# 5_-Keyboard.net
KiCad netlist of a schematic drawn in Altium Designer
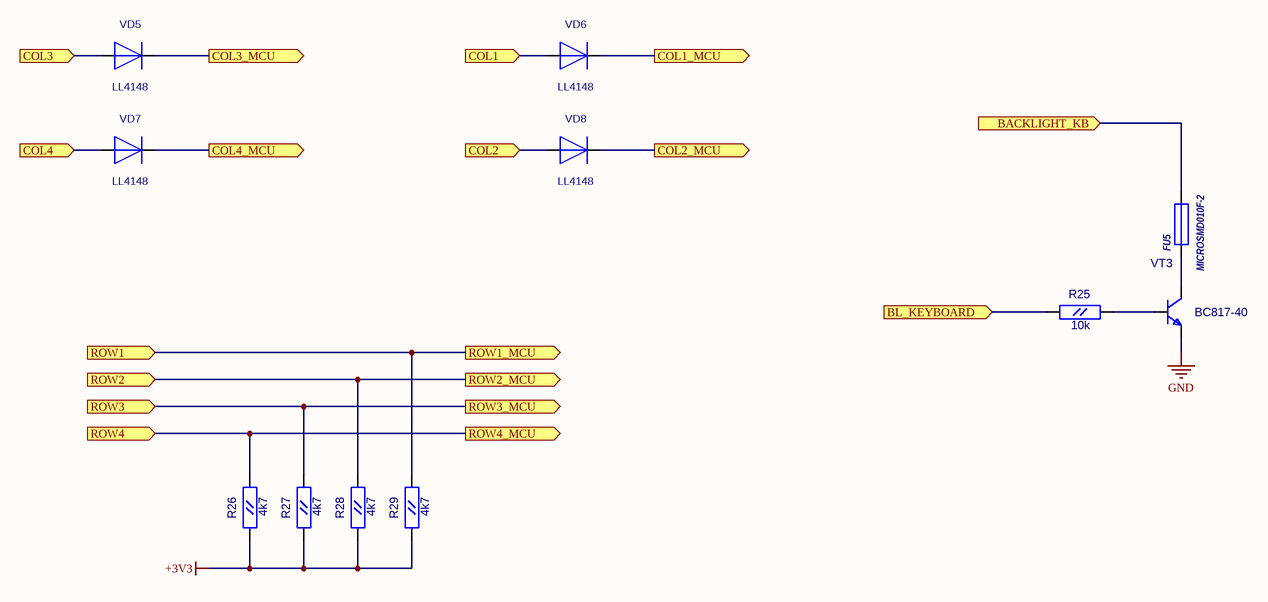
[diagram p0: [5]-Keyboard.SchDoc]

(export (version "E")
  (design (tool "Eeschema 10.0.6"))
  (components
    (comp (ref "FU5")
      (value "MICROSMD010F-2")
      (footprint "RC1210")
      (description "MICROSMD")
      (libsource (lib "gprs_modem_2") (part "MICROSMD"))
    )
    (comp (ref "R25")
      (value "10k")
      (footprint "RC0603")
      (description "RC0603")
      (libsource (lib "gprs_modem_2") (part "RC0603"))
    )
    (comp (ref "R26")
      (value "4k7")
      (footprint "RC0603")
      (description "RC0603")
      (libsource (lib "gprs_modem_2") (part "RC0603"))
    )
    (comp (ref "R27")
      (value "4k7")
      (footprint "RC0603")
      (description "RC0603")
      (libsource (lib "gprs_modem_2") (part "RC0603"))
    )
    (comp (ref "R28")
      (value "4k7")
      (footprint "RC0603")
      (description "RC0603")
      (libsource (lib "gprs_modem_2") (part "RC0603"))
    )
    (comp (ref "R29")
      (value "4k7")
      (footprint "RC0603")
      (description "RC0603")
      (libsource (lib "gprs_modem_2") (part "RC0603"))
    )
    (comp (ref "VD5") (value "LL4148") (footprint "SOD-80") (libsource (lib "gprs_modem_2") (part "LL4148")))
    (comp (ref "VD6") (value "LL4148") (footprint "SOD-80") (libsource (lib "gprs_modem_2") (part "LL4148")))
    (comp (ref "VD7") (value "LL4148") (footprint "SOD-80") (libsource (lib "gprs_modem_2") (part "LL4148")))
    (comp (ref "VD8") (value "LL4148") (footprint "SOD-80") (libsource (lib "gprs_modem_2") (part "LL4148")))
    (comp (ref "VT3")
      (value "BC817-40")
      (footprint "SOT-23(123)")
      (description "NPN 500ma transistor")
      (libsource (lib "gprs_modem_2") (part "BC846BLT1"))
    )
  )
  (nets
    (net (code "1") (name "+3V3") (class "Default")
      (node (ref "R26") (pin "1") (pinfunction "A_1") (pintype "passive"))
      (node (ref "R27") (pin "1") (pinfunction "A_1") (pintype "passive"))
      (node (ref "R28") (pin "1") (pinfunction "A_1") (pintype "passive"))
      (node (ref "R29") (pin "1") (pinfunction "A_1") (pintype "passive"))
    )
    (net (code "2") (name "/BACKLIGHT_KB") (class "Default") (node (ref "FU5") (pin "2") (pintype "passive")))
    (net (code "3") (name "/BL_KEYBOARD") (class "Default")
      (node (ref "R25") (pin "1") (pinfunction "A_1") (pintype "passive"))
    )
    (net (code "4") (name "/COL1") (class "Default")
      (node (ref "VD6") (pin "1") (pinfunction "-_1") (pintype "passive"))
    )
    (net (code "5") (name "/COL1_MCU") (class "Default")
      (node (ref "VD6") (pin "2") (pinfunction "+_2") (pintype "passive"))
    )
    (net (code "6") (name "/COL2") (class "Default")
      (node (ref "VD8") (pin "1") (pinfunction "-_1") (pintype "passive"))
    )
    (net (code "7") (name "/COL2_MCU") (class "Default")
      (node (ref "VD8") (pin "2") (pinfunction "+_2") (pintype "passive"))
    )
    (net (code "8") (name "/COL3") (class "Default")
      (node (ref "VD5") (pin "1") (pinfunction "-_1") (pintype "passive"))
    )
    (net (code "9") (name "/COL3_MCU") (class "Default")
      (node (ref "VD5") (pin "2") (pinfunction "+_2") (pintype "passive"))
    )
    (net (code "10") (name "/COL4") (class "Default")
      (node (ref "VD7") (pin "1") (pinfunction "-_1") (pintype "passive"))
    )
    (net (code "11") (name "/COL4_MCU") (class "Default")
      (node (ref "VD7") (pin "2") (pinfunction "+_2") (pintype "passive"))
    )
    (net (code "12") (name "/ROW1") (class "Default")
      (node (ref "R29") (pin "2") (pinfunction "B_2") (pintype "passive"))
    )
    (net (code "13") (name "/ROW2") (class "Default")
      (node (ref "R28") (pin "2") (pinfunction "B_2") (pintype "passive"))
    )
    (net (code "14") (name "/ROW3") (class "Default")
      (node (ref "R27") (pin "2") (pinfunction "B_2") (pintype "passive"))
    )
    (net (code "15") (name "/ROW4") (class "Default")
      (node (ref "R26") (pin "2") (pinfunction "B_2") (pintype "passive"))
    )
    (net (code "16") (name "GND") (class "Default")
      (node (ref "VT3") (pin "2") (pinfunction "E_2") (pintype "passive"))
    )
    (net (code "17") (name "Net-(R25-B)") (class "Default")
      (node (ref "R25") (pin "2") (pinfunction "B_2") (pintype "passive"))
      (node (ref "VT3") (pin "1") (pinfunction "B_1") (pintype "passive"))
    )
    (net (code "18") (name "Net-(VT3-C)") (class "Default")
      (node (ref "FU5") (pin "1") (pintype "passive"))
      (node (ref "VT3") (pin "3") (pinfunction "C_3") (pintype "passive"))
    )
  )
)
